# BMSMaster.net
KiCad netlist of a schematic drawn in EAGLE
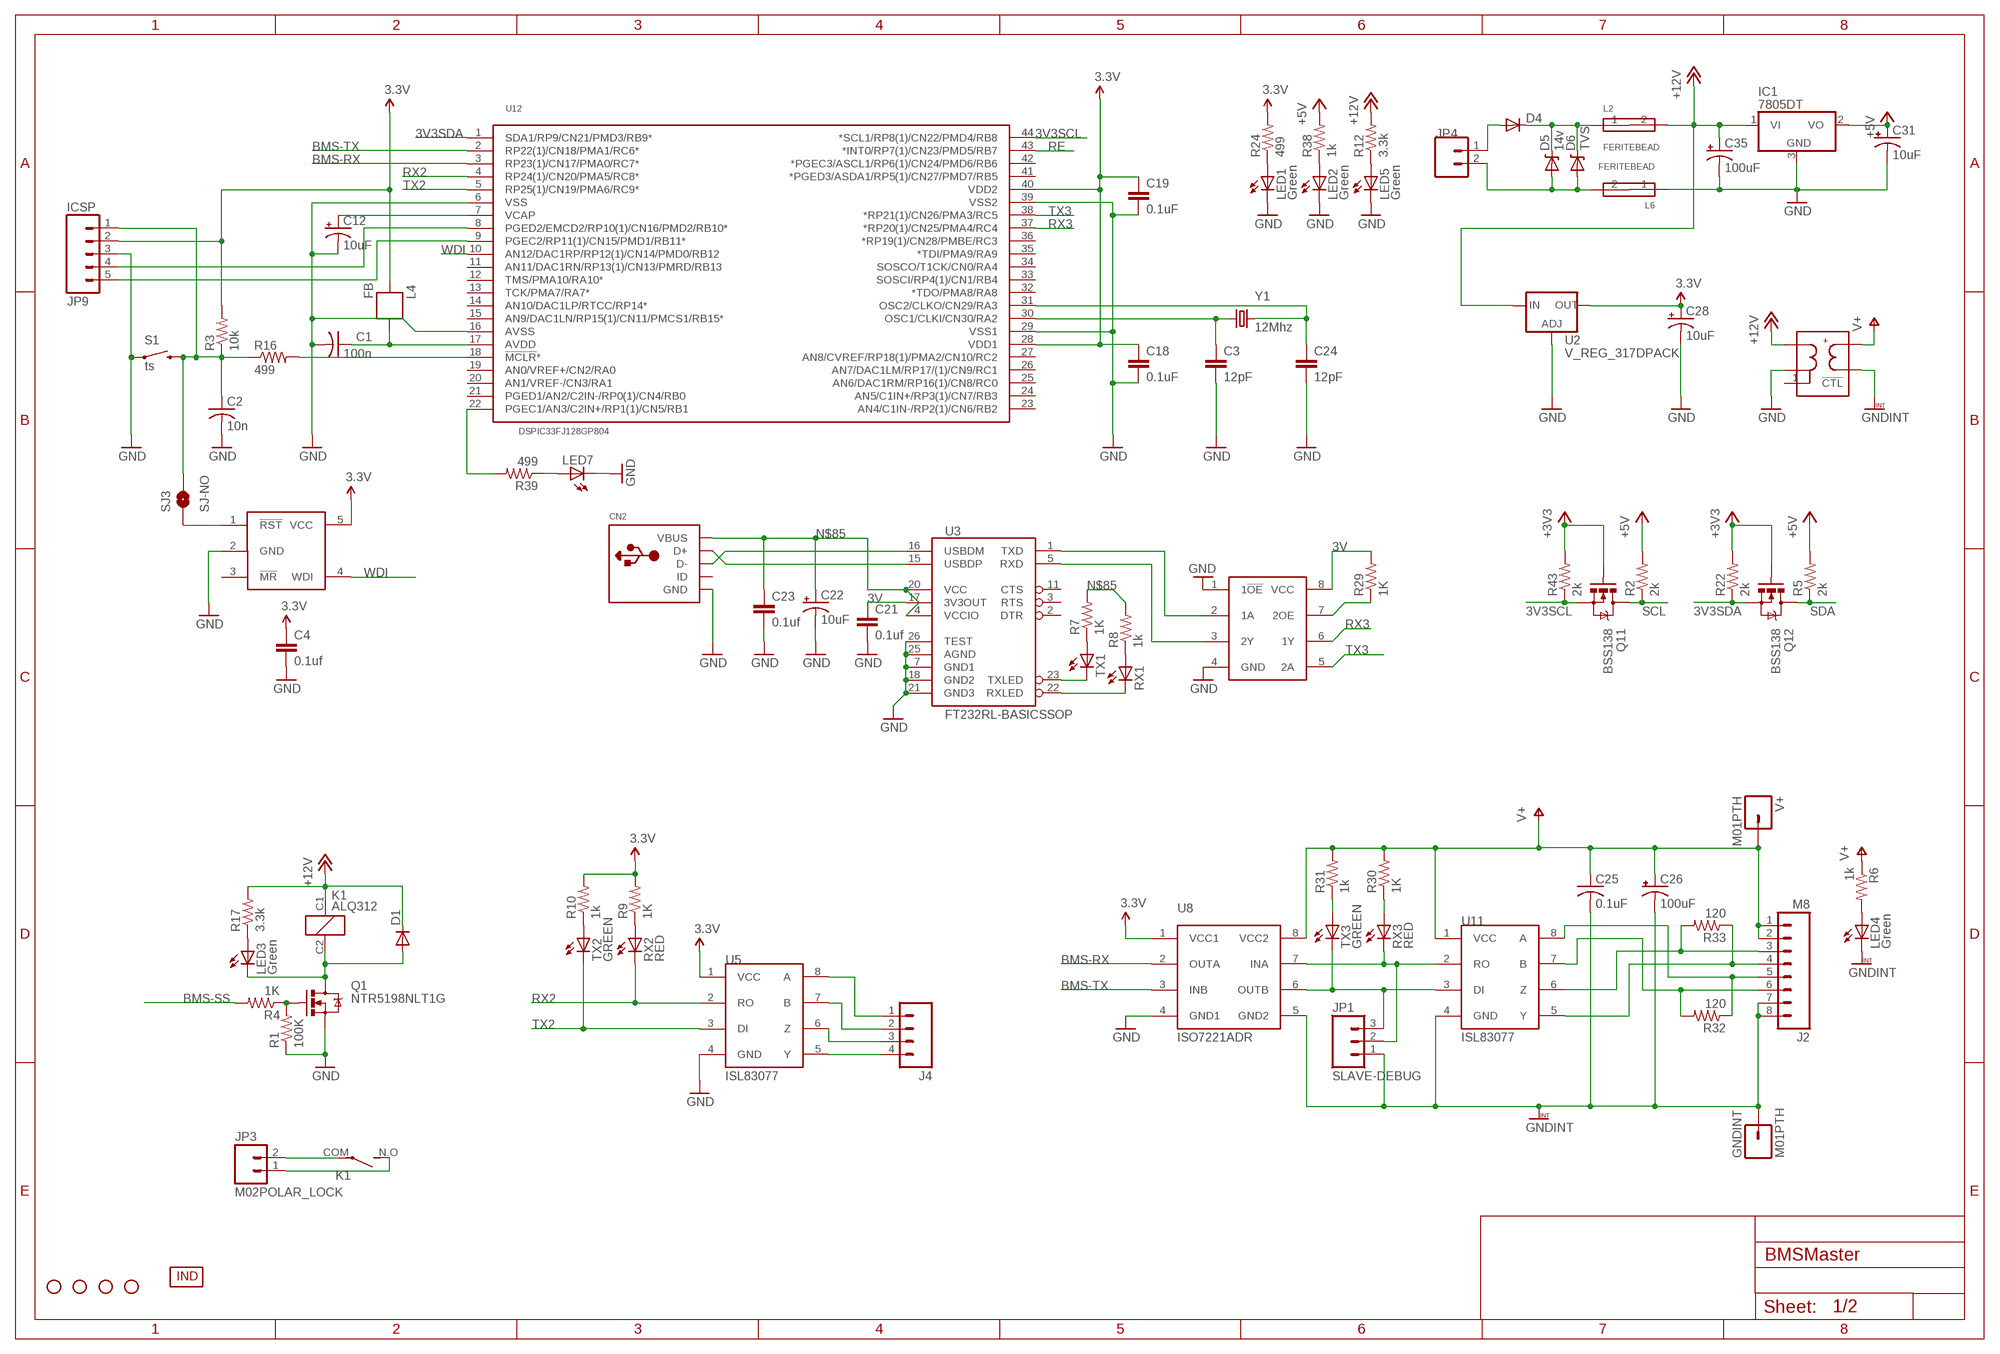
[diagram p0: schematic, sheet 1]
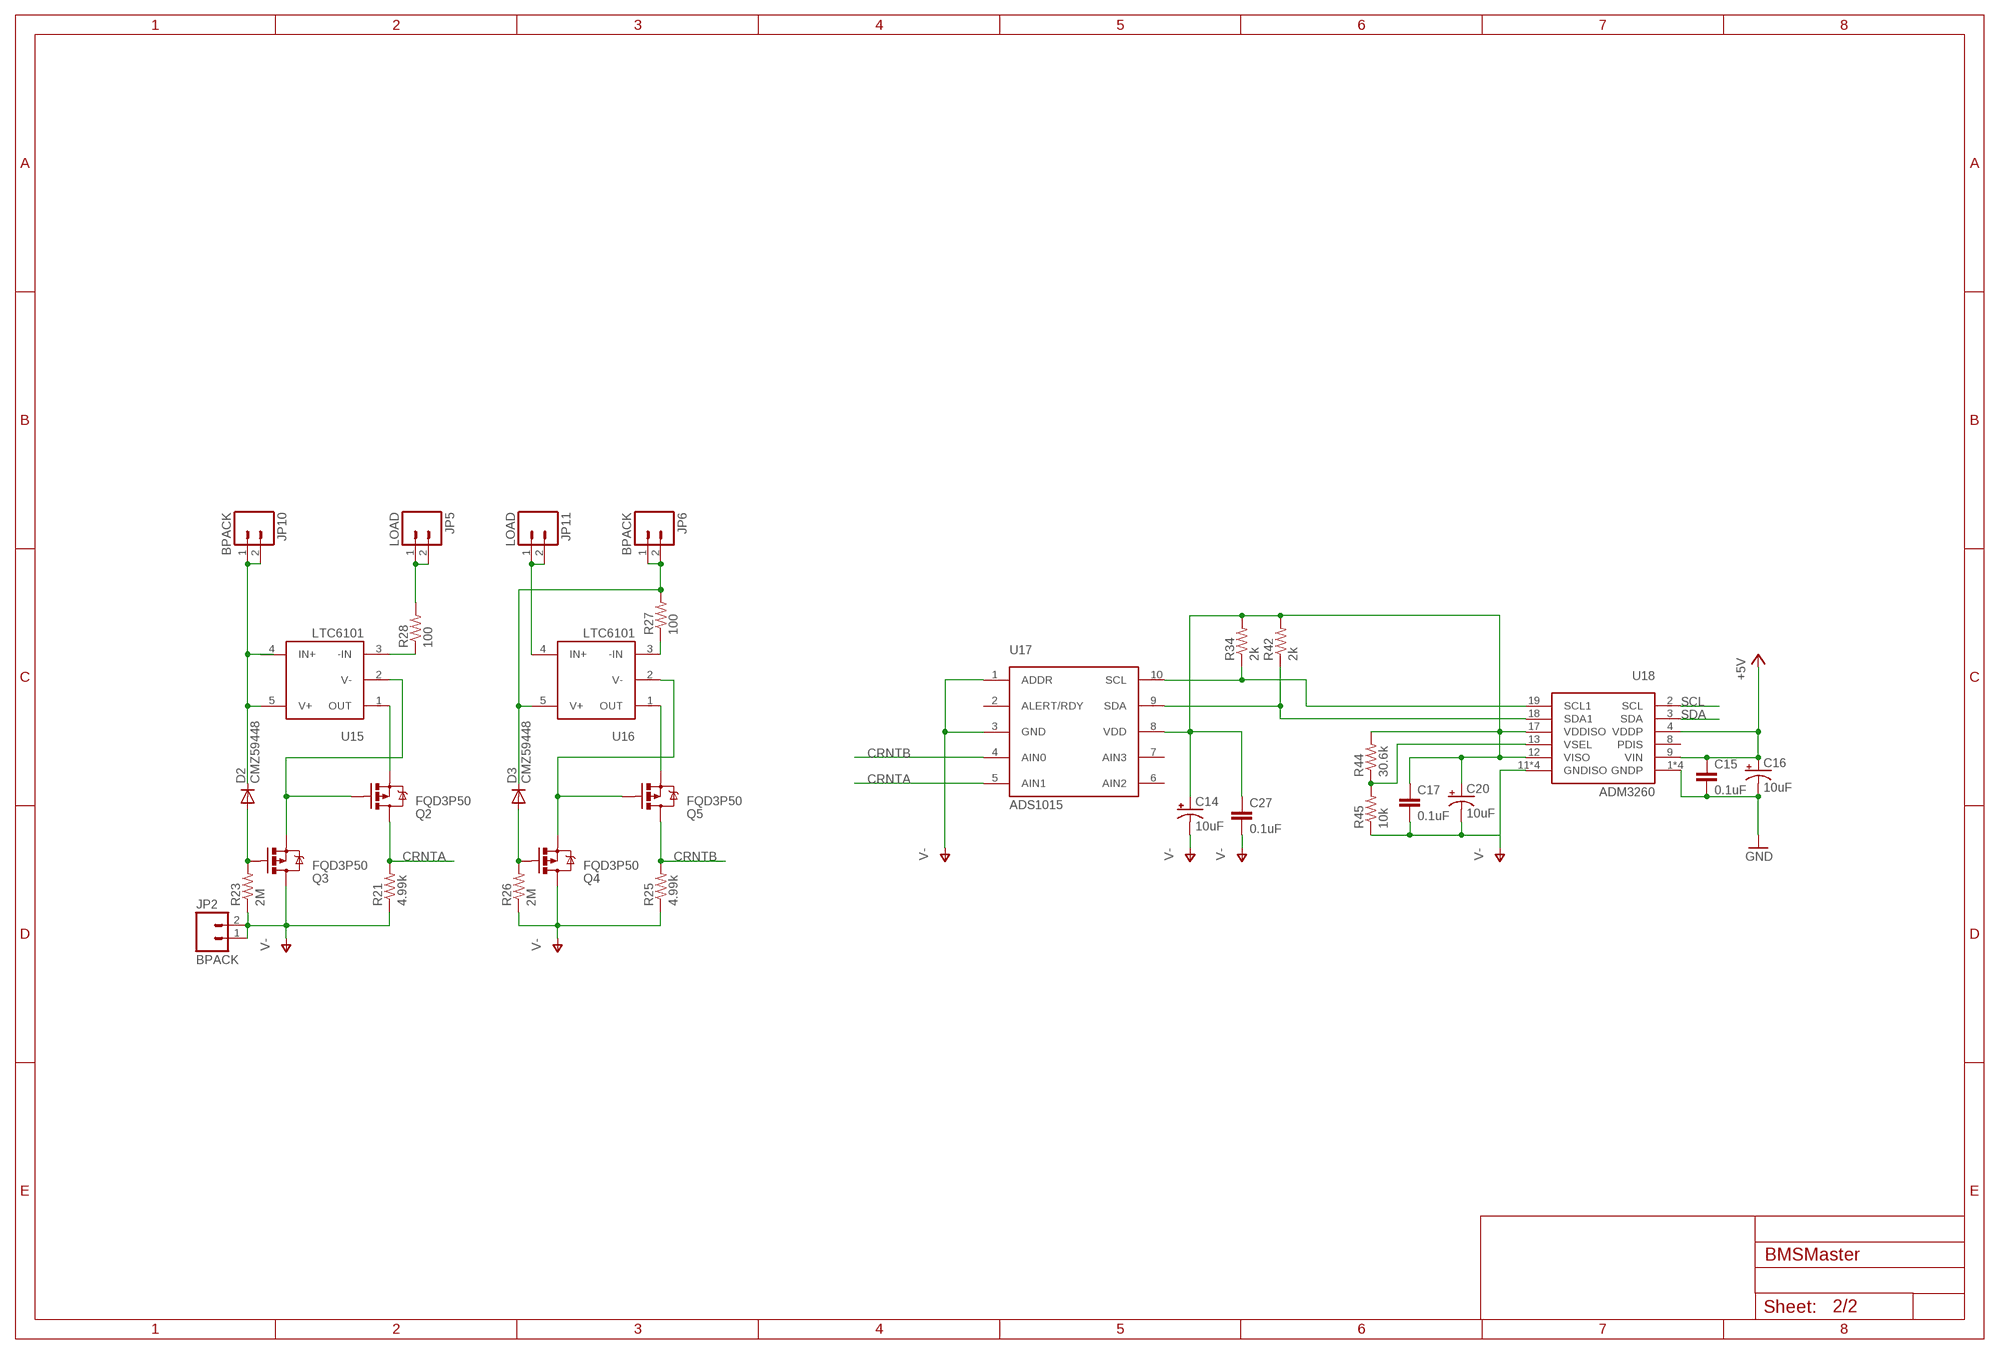
[diagram p1: schematic, sheet 2]

(export (version "E")
  (design (tool "Eeschema 10.0.6"))
  (components
    (comp (ref "C14")
      (value "10uF")
      (footprint "eagle-import:EIA3216")
      (libsource (lib "eagle-import") (part "SparkFun-Capacitors_CAP_POL1206"))
    )
    (comp (ref "C15")
      (value "0.1uF")
      (footprint "eagle-import:0805")
      (libsource (lib "eagle-import") (part "SparkFun-Capacitors_CAP0805"))
    )
    (comp (ref "C16")
      (value "10uF")
      (footprint "eagle-import:EIA3216")
      (libsource (lib "eagle-import") (part "SparkFun-Capacitors_CAP_POL1206"))
    )
    (comp (ref "C17")
      (value "0.1uF")
      (footprint "eagle-import:0805")
      (libsource (lib "eagle-import") (part "SparkFun-Capacitors_CAP0805"))
    )
    (comp (ref "C20")
      (value "10uF")
      (footprint "eagle-import:EIA3216")
      (libsource (lib "eagle-import") (part "SparkFun-Capacitors_CAP_POL1206"))
    )
    (comp (ref "C27")
      (value "0.1uF")
      (footprint "eagle-import:0805")
      (libsource (lib "eagle-import") (part "SparkFun-Capacitors_CAP0805"))
    )
    (comp (ref "D2")
      (value "CMZ59448")
      (footprint "eagle-import:DIODE-HV")
      (libsource (lib "eagle-import") (part "DIODEHV"))
    )
    (comp (ref "D3")
      (value "CMZ59448")
      (footprint "eagle-import:DIODE-HV")
      (libsource (lib "eagle-import") (part "DIODEHV"))
    )
    (comp (ref "JP2")
      (value "BPACK")
      (footprint "eagle-import:MOLEX-1X2_LOCK")
      (libsource (lib "eagle-import") (part "M02POLAR_LOCK"))
    )
    (comp (ref "JP5")
      (value "LOAD")
      (footprint "eagle-import:MOLEX-1X2_LOCK")
      (libsource (lib "eagle-import") (part "M02POLAR_LOCK"))
    )
    (comp (ref "JP6")
      (value "BPACK")
      (footprint "eagle-import:MOLEX-1X2_LOCK")
      (libsource (lib "eagle-import") (part "M02POLAR_LOCK"))
    )
    (comp (ref "JP10")
      (value "BPACK")
      (footprint "eagle-import:MOLEX-1X2_LOCK")
      (libsource (lib "eagle-import") (part "M02POLAR_LOCK"))
    )
    (comp (ref "JP11")
      (value "LOAD")
      (footprint "eagle-import:MOLEX-1X2_LOCK")
      (libsource (lib "eagle-import") (part "M02POLAR_LOCK"))
    )
    (comp (ref "Q2")
      (value "FQD3P50")
      (footprint "eagle-import:DPAK")
      (libsource (lib "eagle-import") (part "FQD3P50"))
    )
    (comp (ref "Q3")
      (value "FQD3P50")
      (footprint "eagle-import:DPAK")
      (libsource (lib "eagle-import") (part "FQD3P50"))
    )
    (comp (ref "Q4")
      (value "FQD3P50")
      (footprint "eagle-import:DPAK")
      (libsource (lib "eagle-import") (part "FQD3P50"))
    )
    (comp (ref "Q5")
      (value "FQD3P50")
      (footprint "eagle-import:DPAK")
      (libsource (lib "eagle-import") (part "FQD3P50"))
    )
    (comp (ref "R21")
      (value "4.99k")
      (footprint "eagle-import:1206")
      (libsource (lib "eagle-import") (part "RESISTOR1206"))
    )
    (comp (ref "R23")
      (value "2M")
      (footprint "eagle-import:1206")
      (libsource (lib "eagle-import") (part "RESISTOR1206"))
    )
    (comp (ref "R25")
      (value "4.99k")
      (footprint "eagle-import:1206")
      (libsource (lib "eagle-import") (part "RESISTOR1206"))
    )
    (comp (ref "R26")
      (value "2M")
      (footprint "eagle-import:1206")
      (libsource (lib "eagle-import") (part "RESISTOR1206"))
    )
    (comp (ref "R27")
      (value "100")
      (footprint "eagle-import:1206")
      (libsource (lib "eagle-import") (part "RESISTOR1206"))
    )
    (comp (ref "R28")
      (value "100")
      (footprint "eagle-import:1206")
      (libsource (lib "eagle-import") (part "RESISTOR1206"))
    )
    (comp (ref "R34")
      (value "2k")
      (footprint "eagle-import:0805")
      (libsource (lib "eagle-import") (part "RESISTOR0805-RES"))
    )
    (comp (ref "R42")
      (value "2k")
      (footprint "eagle-import:0805")
      (libsource (lib "eagle-import") (part "RESISTOR0805-RES"))
    )
    (comp (ref "R44")
      (value "30.6k")
      (footprint "eagle-import:0805")
      (libsource (lib "eagle-import") (part "RESISTOR0805-RES"))
    )
    (comp (ref "R45")
      (value "10k")
      (footprint "eagle-import:0805")
      (libsource (lib "eagle-import") (part "RESISTOR0805-RES"))
    )
    (comp (ref "U15")
      (value "LTC6101")
      (footprint "eagle-import:SOT23-5")
      (libsource (lib "eagle-import") (part "LTC6101"))
    )
    (comp (ref "U16")
      (value "LTC6101")
      (footprint "eagle-import:SOT23-5")
      (libsource (lib "eagle-import") (part "LTC6101"))
    )
    (comp (ref "U17")
      (value "ADS1015")
      (footprint "eagle-import:MSOP-10")
      (libsource (lib "eagle-import") (part "ADS1015"))
    )
    (comp (ref "U18")
      (value "ADM3260")
      (footprint "eagle-import:SSOP-20")
      (libsource (lib "eagle-import") (part "ADM3260"))
    )
    (comp (ref "C1")
      (value "100n")
      (footprint "eagle-import:C0805")
      (libsource (lib "eagle-import") (part "C-USC0805"))
    )
    (comp (ref "C2")
      (value "10n")
      (footprint "eagle-import:C0805")
      (libsource (lib "eagle-import") (part "C-USC0805"))
    )
    (comp (ref "C3")
      (value "12pF")
      (footprint "eagle-import:0805")
      (libsource (lib "eagle-import") (part "SparkFun-Capacitors_CAP0805"))
    )
    (comp (ref "C4")
      (value "0.1uf")
      (footprint "eagle-import:0805")
      (libsource (lib "eagle-import") (part "CAP0805"))
    )
    (comp (ref "C12")
      (value "10uF")
      (footprint "eagle-import:EIA3216")
      (libsource (lib "eagle-import") (part "10UF-TANT"))
    )
    (comp (ref "C18")
      (value "0.1uF")
      (footprint "eagle-import:0805")
      (libsource (lib "eagle-import") (part "SparkFun-Capacitors_CAP0805"))
    )
    (comp (ref "C19")
      (value "0.1uF")
      (footprint "eagle-import:0805")
      (libsource (lib "eagle-import") (part "SparkFun-Capacitors_CAP0805"))
    )
    (comp (ref "C21")
      (value "0.1uf")
      (footprint "eagle-import:0805")
      (libsource (lib "eagle-import") (part "CAP0805"))
    )
    (comp (ref "C22")
      (value "10uF")
      (footprint "eagle-import:EIA3216")
      (libsource (lib "eagle-import") (part "CAP_POL1206"))
    )
    (comp (ref "C23")
      (value "0.1uf")
      (footprint "eagle-import:0805")
      (libsource (lib "eagle-import") (part "CAP0805"))
    )
    (comp (ref "C24")
      (value "12pF")
      (footprint "eagle-import:0805")
      (libsource (lib "eagle-import") (part "SparkFun-Capacitors_CAP0805"))
    )
    (comp (ref "C25")
      (value "0.1uF")
      (footprint "eagle-import:C0805")
      (libsource (lib "eagle-import") (part "rcl_C-USC0805"))
    )
    (comp (ref "C26")
      (value "100uF")
      (footprint "eagle-import:C_6032-28W")
      (libsource (lib "eagle-import") (part "rcl_CPOL-USC/6032-28W"))
    )
    (comp (ref "C28")
      (value "10uF")
      (footprint "eagle-import:POLC1206")
      (libsource (lib "eagle-import") (part "POLCAP"))
    )
    (comp (ref "C31")
      (value "10uF")
      (footprint "eagle-import:EIA3216")
      (libsource (lib "eagle-import") (part "10UF-16V-10%(TANT)"))
    )
    (comp (ref "C35")
      (value "100uF")
      (footprint "eagle-import:CT7343")
      (libsource (lib "eagle-import") (part "CPOL-USCT7343"))
    )
    (comp (ref "CN2")
      (value "USBMOLEX")
      (footprint "eagle-import:USB-MINIB-THM-MOLEX")
      (libsource (lib "eagle-import") (part "USBMOLEX"))
    )
    (comp (ref "D1")
      (value "DIODESMB")
      (footprint "eagle-import:SMB-DIODE")
      (libsource (lib "eagle-import") (part "DIODESMB"))
    )
    (comp (ref "D4")
      (value "DIODESMA")
      (footprint "eagle-import:SMA-DIODE")
      (libsource (lib "eagle-import") (part "DIODESMA"))
    )
    (comp (ref "D5")
      (value "14v")
      (footprint "eagle-import:SMB-DIODE")
      (libsource (lib "eagle-import") (part "DIODE-ZENERSMB"))
    )
    (comp (ref "D6")
      (value "TVS")
      (footprint "eagle-import:DO-214AC")
      (libsource (lib "eagle-import") (part "TVS"))
    )
    (comp (ref "GNDINT")
      (value "M01PTH")
      (footprint "eagle-import:1X01")
      (libsource (lib "eagle-import") (part "M01PTH"))
    )
    (comp (ref "IC1")
      (value "7805DT")
      (footprint "eagle-import:TO252")
      (libsource (lib "eagle-import") (part "78DT05"))
    )
    (comp (ref "J2")
      (value "M8")
      (footprint "eagle-import:75869-132LF")
      (libsource (lib "eagle-import") (part "M8"))
    )
    (comp (ref "J4")
      (value "M04POLAR_LOCK")
      (footprint "eagle-import:MOLEX-1X4_LOCK")
      (libsource (lib "eagle-import") (part "M04POLAR_LOCK"))
    )
    (comp (ref "JP1")
      (value "SLAVE-DEBUG")
      (footprint "eagle-import:1X03_LOCK_LONGPADS")
      (libsource (lib "eagle-import") (part "M03LOCK_LONGPADS"))
    )
    (comp (ref "JP3")
      (value "M02POLAR_LOCK")
      (footprint "eagle-import:MOLEX-1X2_LOCK")
      (libsource (lib "eagle-import") (part "M02POLAR_LOCK"))
    )
    (comp (ref "JP4")
      (value "M02POLAR_LOCK")
      (footprint "eagle-import:MOLEX-1X2_LOCK")
      (libsource (lib "eagle-import") (part "M02POLAR_LOCK"))
    )
    (comp (ref "JP9")
      (value "ICSP")
      (footprint "eagle-import:1X05_LOCK_LONGPADS")
      (libsource (lib "eagle-import") (part "M05LOCK_LONGPADS"))
    )
    (comp (ref "K1")
      (value "ALQ312")
      (footprint "eagle-import:ALQ312")
      (libsource (lib "eagle-import") (part "ALQ312"))
    )
    (comp (ref "L2")
      (value "FERITEBEAD")
      (footprint "eagle-import:0603")
      (libsource (lib "eagle-import") (part "FERITEBEAD"))
    )
    (comp (ref "L4")
      (value "FB")
      (footprint "eagle-import:0603")
      (libsource (lib "eagle-import") (part "FB"))
    )
    (comp (ref "L6")
      (value "FERITEBEAD")
      (footprint "eagle-import:0603")
      (libsource (lib "eagle-import") (part "FERITEBEAD"))
    )
    (comp (ref "LED1")
      (value "Green")
      (footprint "eagle-import:CHIPLED_0805")
      (libsource (lib "eagle-import") (part "LEDCHIPLED_0805"))
    )
    (comp (ref "LED2")
      (value "Green")
      (footprint "eagle-import:CHIPLED_0805")
      (libsource (lib "eagle-import") (part "LEDCHIPLED_0805"))
    )
    (comp (ref "LED3")
      (value "Green")
      (footprint "eagle-import:CHIPLED_0805")
      (libsource (lib "eagle-import") (part "LEDCHIPLED_0805"))
    )
    (comp (ref "LED4")
      (value "Green")
      (footprint "eagle-import:CHIPLED_0805")
      (libsource (lib "eagle-import") (part "LEDCHIPLED_0805"))
    )
    (comp (ref "LED5")
      (value "Green")
      (footprint "eagle-import:CHIPLED_0805")
      (libsource (lib "eagle-import") (part "LEDCHIPLED_0805"))
    )
    (comp (ref "LED7")
      (value "LEDCHIP-LED0805")
      (footprint "eagle-import:CHIP-LED0805")
      (libsource (lib "eagle-import") (part "LEDCHIP-LED0805"))
    )
    (comp (ref "Q1")
      (value "NTR5198NLT1G")
      (footprint "eagle-import:SOT23")
      (libsource (lib "eagle-import") (part "MOSFET-NCHANNELBSS123LT1G"))
    )
    (comp (ref "Q11")
      (value "BSS138")
      (footprint "eagle-import:SOT23-3")
      (libsource (lib "eagle-import") (part "MOSFET-NCHANNELSMD"))
    )
    (comp (ref "Q12")
      (value "BSS138")
      (footprint "eagle-import:SOT23-3")
      (libsource (lib "eagle-import") (part "MOSFET-NCHANNELSMD"))
    )
    (comp (ref "R1")
      (value "100K")
      (footprint "eagle-import:R0805")
      (libsource (lib "eagle-import") (part "R-US_R0805"))
    )
    (comp (ref "R2")
      (value "2k")
      (footprint "eagle-import:R0805")
      (libsource (lib "eagle-import") (part "R-US_R0805"))
    )
    (comp (ref "R3")
      (value "10k")
      (footprint "eagle-import:0805")
      (libsource (lib "eagle-import") (part "RESISTOR0805-RES"))
    )
    (comp (ref "R4")
      (value "1K")
      (footprint "eagle-import:R0805")
      (libsource (lib "eagle-import") (part "R-US_R0805"))
    )
    (comp (ref "R5")
      (value "2k")
      (footprint "eagle-import:R0805")
      (libsource (lib "eagle-import") (part "R-US_R0805"))
    )
    (comp (ref "R6")
      (value "1k")
      (footprint "eagle-import:R0805")
      (libsource (lib "eagle-import") (part "R-US_R0805"))
    )
    (comp (ref "R7")
      (value "1K")
      (footprint "eagle-import:R0805")
      (libsource (lib "eagle-import") (part "R-US_R0805"))
    )
    (comp (ref "R8")
      (value "1k")
      (footprint "eagle-import:R0805")
      (libsource (lib "eagle-import") (part "R-US_R0805"))
    )
    (comp (ref "R9")
      (value "1K")
      (footprint "eagle-import:R0805")
      (libsource (lib "eagle-import") (part "R-US_R0805"))
    )
    (comp (ref "R10")
      (value "1k")
      (footprint "eagle-import:R0805")
      (libsource (lib "eagle-import") (part "R-US_R0805"))
    )
    (comp (ref "R12")
      (value "3.3k")
      (footprint "eagle-import:R0805")
      (libsource (lib "eagle-import") (part "R-US_R0805"))
    )
    (comp (ref "R16")
      (value "499")
      (footprint "eagle-import:0805")
      (libsource (lib "eagle-import") (part "SparkFun-Resistors_RESISTOR0805-RES"))
    )
    (comp (ref "R17")
      (value "3.3k")
      (footprint "eagle-import:R0805")
      (libsource (lib "eagle-import") (part "R-US_R0805"))
    )
    (comp (ref "R22")
      (value "2k")
      (footprint "eagle-import:R0805")
      (libsource (lib "eagle-import") (part "R-US_R0805"))
    )
    (comp (ref "R24")
      (value "499")
      (footprint "eagle-import:R0805")
      (libsource (lib "eagle-import") (part "R-US_R0805"))
    )
    (comp (ref "R29")
      (value "1K")
      (footprint "eagle-import:R0805")
      (libsource (lib "eagle-import") (part "R-US_R0805"))
    )
    (comp (ref "R30")
      (value "1K")
      (footprint "eagle-import:R0805")
      (libsource (lib "eagle-import") (part "R-US_R0805"))
    )
    (comp (ref "R31")
      (value "1k")
      (footprint "eagle-import:R0805")
      (libsource (lib "eagle-import") (part "R-US_R0805"))
    )
    (comp (ref "R32")
      (value "120")
      (footprint "eagle-import:R0805")
      (libsource (lib "eagle-import") (part "R-US_R0805"))
    )
    (comp (ref "R33")
      (value "120")
      (footprint "eagle-import:R0805")
      (libsource (lib "eagle-import") (part "R-US_R0805"))
    )
    (comp (ref "R38")
      (value "1k")
      (footprint "eagle-import:R0805")
      (libsource (lib "eagle-import") (part "R-US_R0805"))
    )
    (comp (ref "R39")
      (value "499")
      (footprint "eagle-import:0805")
      (libsource (lib "eagle-import") (part "RESISTOR0805-RES"))
    )
    (comp (ref "R43")
      (value "2k")
      (footprint "eagle-import:R0805")
      (libsource (lib "eagle-import") (part "R-US_R0805"))
    )
    (comp (ref "RX1")
      (value "LEDCHIPLED_0805")
      (footprint "eagle-import:CHIPLED_0805")
      (libsource (lib "eagle-import") (part "LEDCHIPLED_0805"))
    )
    (comp (ref "RX2")
      (value "RED")
      (footprint "eagle-import:CHIPLED_0805")
      (libsource (lib "eagle-import") (part "LEDCHIPLED_0805"))
    )
    (comp (ref "RX3")
      (value "RED")
      (footprint "eagle-import:CHIPLED_0805")
      (libsource (lib "eagle-import") (part "LEDCHIPLED_0805"))
    )
    (comp (ref "S1")
      (value "ts")
      (footprint "eagle-import:TACTILE-PTH-SIDEEZ")
      (libsource (lib "eagle-import") (part "SWITCH-MOMENTARY-2SIDE_EZ"))
    )
    (comp (ref "SJ3")
      (value "SJ-NO")
      (footprint "eagle-import:SJ_2S-NO")
      (libsource (lib "eagle-import") (part "SOLDERJUMPERNO"))
    )
    (comp (ref "STANDOFF1")
      (value "STAND-OFF")
      (footprint "eagle-import:STAND-OFF")
      (libsource (lib "eagle-import") (part "STAND-OFF"))
    )
    (comp (ref "STANDOFF2")
      (value "STAND-OFF")
      (footprint "eagle-import:STAND-OFF")
      (libsource (lib "eagle-import") (part "STAND-OFF"))
    )
    (comp (ref "STANDOFF3")
      (value "STAND-OFF")
      (footprint "eagle-import:STAND-OFF")
      (libsource (lib "eagle-import") (part "STAND-OFF"))
    )
    (comp (ref "STANDOFF4")
      (value "STAND-OFF")
      (footprint "eagle-import:STAND-OFF")
      (libsource (lib "eagle-import") (part "STAND-OFF"))
    )
    (comp (ref "TX1")
      (value "LEDCHIPLED_0805")
      (footprint "eagle-import:CHIPLED_0805")
      (libsource (lib "eagle-import") (part "LEDCHIPLED_0805"))
    )
    (comp (ref "TX2")
      (value "GREEN")
      (footprint "eagle-import:CHIPLED_0805")
      (libsource (lib "eagle-import") (part "LEDCHIPLED_0805"))
    )
    (comp (ref "TX3")
      (value "GREEN")
      (footprint "eagle-import:CHIPLED_0805")
      (libsource (lib "eagle-import") (part "LEDCHIPLED_0805"))
    )
    (comp (ref "U$1")
      (value "INDPK1")
      (footprint "eagle-import:PICKIT-PIN-1")
      (libsource (lib "eagle-import") (part "INDPK1"))
    )
    (comp (ref "U2")
      (value "V_REG_317DPACK")
      (footprint "eagle-import:V-REG_DPACK")
      (libsource (lib "eagle-import") (part "V_REG_317DPACK"))
    )
    (comp (ref "U3")
      (value "FT232RL-BASICSSOP")
      (footprint "eagle-import:SSOP28DB")
      (libsource (lib "eagle-import") (part "FT232RL-BASICSSOP"))
    )
    (comp (ref "U4")
      (value "SN74LVC2G241DCTR")
      (footprint "eagle-import:VFSOP-8")
      (libsource (lib "eagle-import") (part "SN74LVC2G241DCTR"))
    )
    (comp (ref "U5")
      (value "ISL83077")
      (footprint "eagle-import:SO08")
      (libsource (lib "eagle-import") (part "ISL83077"))
    )
    (comp (ref "U8")
      (value "ISO7221ADR")
      (footprint "eagle-import:SOIC-8")
      (libsource (lib "eagle-import") (part "ISO7221ADR"))
    )
    (comp (ref "U9")
      (value "MAX823")
      (footprint "eagle-import:SOT23-5L")
      (libsource (lib "eagle-import") (part "MAX823"))
    )
    (comp (ref "U11")
      (value "ISL83077")
      (footprint "eagle-import:SO08")
      (libsource (lib "eagle-import") (part "ISL83077"))
    )
    (comp (ref "U12")
      (value "DSPIC33FJ128GP804")
      (footprint "eagle-import:TQFP-44")
      (libsource (lib "eagle-import") (part "DSPIC33FJ128GP804"))
    )
    (comp (ref "U21")
      (value "REC7.5-1205SRW/H2/A/M")
      (footprint "eagle-import:24DIPMOD-8LEAD")
      (libsource (lib "eagle-import") (part "REC7.5-1205SRW/H2/A/M"))
    )
    (comp (ref "V+")
      (value "M01PTH")
      (footprint "eagle-import:1X01")
      (libsource (lib "eagle-import") (part "M01PTH"))
    )
    (comp (ref "Y1")
      (value "12Mhz")
      (footprint "eagle-import:CRYSTAL-SMD-5X3")
      (libsource (lib "eagle-import") (part "CRYSTAL5X3"))
    )
  )
  (nets
    (net (code "1") (name "+3V3") (class "Default")
      (node (ref "Q11") (pin "1") (pinfunction "G_1") (pintype "passive"))
      (node (ref "Q12") (pin "1") (pinfunction "G_1") (pintype "passive"))
      (node (ref "R22") (pin "2") (pinfunction "2_2") (pintype "passive"))
      (node (ref "R43") (pin "2") (pinfunction "2_2") (pintype "passive"))
    )
    (net (code "2") (name "+5V") (class "Default")
      (node (ref "C15") (pin "1") (pinfunction "1_1") (pintype "passive"))
      (node (ref "C16") (pin "A") (pinfunction "+_A") (pintype "passive"))
      (node (ref "C31") (pin "A") (pinfunction "+_A") (pintype "passive"))
      (node (ref "IC1") (pin "2") (pinfunction "VO_2") (pintype "passive"))
      (node (ref "R2") (pin "2") (pinfunction "2_2") (pintype "passive"))
      (node (ref "R38") (pin "2") (pinfunction "2_2") (pintype "passive"))
      (node (ref "R5") (pin "2") (pinfunction "2_2") (pintype "passive"))
      (node (ref "U18") (pin "4") (pinfunction "VDDP_4") (pintype "bidirectional"))
      (node (ref "U18") (pin "9") (pinfunction "VIN_9") (pintype "bidirectional"))
    )
    (net (code "3") (name "+12V") (class "Default")
      (node (ref "C35") (pin "+") (pinfunction "+_+") (pintype "passive"))
      (node (ref "D1") (pin "C") (pinfunction "C_C") (pintype "passive"))
      (node (ref "IC1") (pin "1") (pinfunction "VI_1") (pintype "input"))
      (node (ref "K1") (pin "C1") (pinfunction "+_C1") (pintype "passive"))
      (node (ref "L2") (pin "2") (pinfunction "P$2_2") (pintype "bidirectional"))
      (node (ref "R12") (pin "2") (pinfunction "2_2") (pintype "passive"))
      (node (ref "R17") (pin "2") (pinfunction "2_2") (pintype "passive"))
      (node (ref "U2") (pin "3") (pinfunction "IN_3") (pintype "input"))
      (node (ref "U21") (pin "22") (pinfunction "VIN+_22") (pintype "bidirectional"))
      (node (ref "U21") (pin "23") (pinfunction "VIN+_23") (pintype "bidirectional"))
    )
    (net (code "4") (name "3.3V") (class "Default")
      (node (ref "C18") (pin "1") (pinfunction "1_1") (pintype "passive"))
      (node (ref "C19") (pin "1") (pinfunction "1_1") (pintype "passive"))
      (node (ref "C28") (pin "1") (pinfunction "+_1") (pintype "passive"))
      (node (ref "C4") (pin "1") (pinfunction "1_1") (pintype "passive"))
      (node (ref "JP9") (pin "2") (pinfunction "2_2") (pintype "passive"))
      (node (ref "L4") (pin "2") (pinfunction "P$2_2") (pintype "bidirectional"))
      (node (ref "R10") (pin "2") (pinfunction "2_2") (pintype "passive"))
      (node (ref "R24") (pin "2") (pinfunction "2_2") (pintype "passive"))
      (node (ref "R3") (pin "2") (pinfunction "2_2") (pintype "passive"))
      (node (ref "R9") (pin "2") (pinfunction "2_2") (pintype "passive"))
      (node (ref "U12") (pin "28") (pinfunction "VDD1_28") (pintype "bidirectional"))
      (node (ref "U12") (pin "40") (pinfunction "VDD2_40") (pintype "bidirectional"))
      (node (ref "U2") (pin "4") (pinfunction "OUT_4") (pintype "output"))
      (node (ref "U5") (pin "1") (pinfunction "VCC_1") (pintype "bidirectional"))
      (node (ref "U8") (pin "1") (pinfunction "VCC1_1") (pintype "bidirectional"))
      (node (ref "U9") (pin "5") (pinfunction "VCC_5") (pintype "bidirectional"))
    )
    (net (code "5") (name "3V") (class "Default")
      (node (ref "C21") (pin "1") (pinfunction "1_1") (pintype "passive"))
      (node (ref "R29") (pin "2") (pinfunction "2_2") (pintype "passive"))
      (node (ref "U3") (pin "17") (pinfunction "3V3OUT_17") (pintype "output"))
      (node (ref "U4") (pin "8") (pinfunction "VCC_8") (pintype "bidirectional"))
    )
    (net (code "6") (name "3V3SCL") (class "Default")
      (node (ref "Q11") (pin "2") (pinfunction "S_2") (pintype "passive"))
      (node (ref "R43") (pin "1") (pinfunction "1_1") (pintype "passive"))
      (node (ref "U12") (pin "44") (pinfunction "*SCL1/RP8(1)/CN22/PMD4/RB8_44") (pintype "bidirectional"))
    )
    (net (code "7") (name "3V3SDA") (class "Default")
      (node (ref "Q12") (pin "2") (pinfunction "S_2") (pintype "passive"))
      (node (ref "R22") (pin "1") (pinfunction "1_1") (pintype "passive"))
      (node (ref "U12") (pin "1") (pinfunction "SDA1/RP9/CN21/PMD3/RB9*_1") (pintype "bidirectional"))
    )
    (net (code "8") (name "BMS-RX") (class "Default")
      (node (ref "U12") (pin "3") (pinfunction "RP23(1)/CN17/PMA0/RC7*_3") (pintype "bidirectional"))
      (node (ref "U8") (pin "2") (pinfunction "OUTA_2") (pintype "bidirectional"))
    )
    (net (code "9") (name "BMS-SS") (class "Default")
      (node (ref "R4") (pin "2") (pinfunction "2_2") (pintype "passive"))
    )
    (net (code "10") (name "BMS-TX") (class "Default")
      (node (ref "U12") (pin "2") (pinfunction "RP22(1)/CN18/PMA1/RC6*_2") (pintype "bidirectional"))
      (node (ref "U8") (pin "3") (pinfunction "INB_3") (pintype "bidirectional"))
    )
    (net (code "11") (name "CRNTA") (class "Default")
      (node (ref "Q2") (pin "2") (pinfunction "D_2") (pintype "passive"))
      (node (ref "R21") (pin "2") (pinfunction "2_2") (pintype "passive"))
      (node (ref "U17") (pin "5") (pinfunction "AIN1_5") (pintype "bidirectional"))
    )
    (net (code "12") (name "CRNTB") (class "Default")
      (node (ref "Q5") (pin "2") (pinfunction "D_2") (pintype "passive"))
      (node (ref "R25") (pin "2") (pinfunction "2_2") (pintype "passive"))
      (node (ref "U17") (pin "4") (pinfunction "AIN0_4") (pintype "bidirectional"))
    )
    (net (code "13") (name "GND") (class "Default")
      (node (ref "C1") (pin "2") (pinfunction "2_2") (pintype "passive"))
      (node (ref "C12") (pin "C") (pinfunction "-_C") (pintype "passive"))
      (node (ref "C15") (pin "2") (pinfunction "2_2") (pintype "passive"))
      (node (ref "C16") (pin "C") (pinfunction "-_C") (pintype "passive"))
      (node (ref "C18") (pin "2") (pinfunction "2_2") (pintype "passive"))
      (node (ref "C19") (pin "2") (pinfunction "2_2") (pintype "passive"))
      (node (ref "C2") (pin "2") (pinfunction "2_2") (pintype "passive"))
      (node (ref "C21") (pin "2") (pinfunction "2_2") (pintype "passive"))
      (node (ref "C22") (pin "C") (pinfunction "-_C") (pintype "passive"))
      (node (ref "C23") (pin "2") (pinfunction "2_2") (pintype "passive"))
      (node (ref "C24") (pin "2") (pinfunction "2_2") (pintype "passive"))
      (node (ref "C28") (pin "2") (pinfunction "-_2") (pintype "passive"))
      (node (ref "C3") (pin "2") (pinfunction "2_2") (pintype "passive"))
      (node (ref "C31") (pin "C") (pinfunction "-_C") (pintype "passive"))
      (node (ref "C35") (pin "-") (pinfunction "-_-") (pintype "passive"))
      (node (ref "C4") (pin "2") (pinfunction "2_2") (pintype "passive"))
      (node (ref "CN2") (pin "GND") (pinfunction "GND_GND") (pintype "power_in"))
      (node (ref "IC1") (pin "3") (pinfunction "GND_3") (pintype "passive"))
      (node (ref "JP9") (pin "3") (pinfunction "3_3") (pintype "passive"))
      (node (ref "L6") (pin "1") (pinfunction "P$1_1") (pintype "bidirectional"))
      (node (ref "LED1") (pin "C") (pinfunction "C_C") (pintype "passive"))
      (node (ref "LED2") (pin "C") (pinfunction "C_C") (pintype "passive"))
      (node (ref "LED5") (pin "C") (pinfunction "C_C") (pintype "passive"))
      (node (ref "LED7") (pin "C") (pinfunction "C_C") (pintype "passive"))
      (node (ref "Q1") (pin "2") (pinfunction "S_2") (pintype "passive"))
      (node (ref "R1") (pin "1") (pinfunction "1_1") (pintype "passive"))
      (node (ref "S1") (pin "1") (pinfunction "1_1") (pintype "passive"))
      (node (ref "U12") (pin "16") (pinfunction "AVSS_16") (pintype "bidirectional"))
      (node (ref "U12") (pin "29") (pinfunction "VSS1_29") (pintype "bidirectional"))
      (node (ref "U12") (pin "39") (pinfunction "VSS2_39") (pintype "bidirectional"))
      (node (ref "U12") (pin "6") (pinfunction "VSS_6") (pintype "bidirectional"))
      (node (ref "U18") (pin "1") (pinfunction "GNDP_1") (pintype "bidirectional"))
      (node (ref "U18") (pin "10") (pinfunction "GNDP_10") (pintype "bidirectional"))
      (node (ref "U18") (pin "5") (pinfunction "GNDP_5") (pintype "bidirectional"))
      (node (ref "U18") (pin "7") (pinfunction "GNDP_7") (pintype "bidirectional"))
      (node (ref "U2") (pin "1") (pinfunction "ADJ_1") (pintype "input"))
      (node (ref "U21") (pin "2") (pinfunction "VIN-_2") (pintype "bidirectional"))
      (node (ref "U21") (pin "3") (pinfunction "VIN-_3") (pintype "bidirectional"))
      (node (ref "U3") (pin "18") (pinfunction "GND2_18") (pintype "power_in"))
      (node (ref "U3") (pin "21") (pinfunction "GND3_21") (pintype "power_in"))
      (node (ref "U3") (pin "25") (pinfunction "AGND_25") (pintype "power_in"))
      (node (ref "U3") (pin "26") (pinfunction "TEST_26") (pintype "input"))
      (node (ref "U3") (pin "7") (pinfunction "GND1_7") (pintype "power_in"))
      (node (ref "U4") (pin "1") (pinfunction "1~{OE}_1") (pintype "bidirectional"))
      (node (ref "U4") (pin "4") (pinfunction "GND_4") (pintype "bidirectional"))
      (node (ref "U5") (pin "4") (pinfunction "GND_4") (pintype "bidirectional"))
      (node (ref "U8") (pin "4") (pinfunction "GND1_4") (pintype "bidirectional"))
      (node (ref "U9") (pin "2") (pinfunction "GND_2") (pintype "bidirectional"))
    )
    (net (code "14") (name "GNDINT") (class "Default")
      (node (ref "C25") (pin "2") (pinfunction "2_2") (pintype "passive"))
      (node (ref "C26") (pin "-") (pinfunction "-_-") (pintype "passive"))
      (node (ref "GNDINT") (pin "1") (pinfunction "1_1") (pintype "passive"))
      (node (ref "J2") (pin "7") (pinfunction "7_7") (pintype "passive"))
      (node (ref "J2") (pin "8") (pinfunction "8_8") (pintype "passive"))
      (node (ref "JP1") (pin "1") (pinfunction "1_1") (pintype "passive"))
      (node (ref "LED4") (pin "C") (pinfunction "C_C") (pintype "passive"))
      (node (ref "U11") (pin "4") (pinfunction "GND_4") (pintype "bidirectional"))
      (node (ref "U21") (pin "16") (pinfunction "VOUT-_16") (pintype "bidirectional"))
      (node (ref "U8") (pin "5") (pinfunction "GND2_5") (pintype "bidirectional"))
    )
    (net (code "15") (name "N$85") (class "Default")
      (node (ref "C22") (pin "A") (pinfunction "+_A") (pintype "passive"))
      (node (ref "C23") (pin "1") (pinfunction "1_1") (pintype "passive"))
      (node (ref "CN2") (pin "VBUS") (pinfunction "VBUS_VBUS") (pintype "power_in"))
      (node (ref "R7") (pin "2") (pinfunction "2_2") (pintype "passive"))
      (node (ref "R8") (pin "2") (pinfunction "2_2") (pintype "passive"))
      (node (ref "U3") (pin "20") (pinfunction "VCC_20") (pintype "power_in"))
      (node (ref "U3") (pin "4") (pinfunction "VCCIO_4") (pintype "power_in"))
    )
    (net (code "16") (name "Net-(C2-Pad1)") (class "Default")
      (node (ref "C2") (pin "1") (pinfunction "1_1") (pintype "passive"))
      (node (ref "JP9") (pin "1") (pinfunction "1_1") (pintype "passive"))
      (node (ref "R16") (pin "1") (pinfunction "1_1") (pintype "passive"))
      (node (ref "R3") (pin "1") (pinfunction "1_1") (pintype "passive"))
      (node (ref "S1") (pin "2") (pinfunction "2_2") (pintype "passive"))
      (node (ref "SJ3") (pin "2") (pinfunction "2_2") (pintype "passive"))
    )
    (net (code "17") (name "Net-(C12-+)") (class "Default")
      (node (ref "C12") (pin "A") (pinfunction "+_A") (pintype "passive"))
      (node (ref "U12") (pin "7") (pinfunction "VCAP_7") (pintype "bidirectional"))
    )
    (net (code "18") (name "Net-(C14-+)") (class "Default")
      (node (ref "C14") (pin "A") (pinfunction "+_A") (pintype "passive"))
      (node (ref "C17") (pin "1") (pinfunction "1_1") (pintype "passive"))
      (node (ref "C20") (pin "A") (pinfunction "+_A") (pintype "passive"))
      (node (ref "C27") (pin "1") (pinfunction "1_1") (pintype "passive"))
      (node (ref "R34") (pin "2") (pinfunction "2_2") (pintype "passive"))
      (node (ref "R42") (pin "2") (pinfunction "2_2") (pintype "passive"))
      (node (ref "R44") (pin "2") (pinfunction "2_2") (pintype "passive"))
      (node (ref "U17") (pin "8") (pinfunction "VDD_8") (pintype "bidirectional"))
      (node (ref "U18") (pin "12") (pinfunction "VISO_12") (pintype "bidirectional"))
      (node (ref "U18") (pin "17") (pinfunction "VDDISO_17") (pintype "bidirectional"))
    )
    (net (code "19") (name "Net-(D4-PadA)") (class "Default")
      (node (ref "D4") (pin "A") (pinfunction "A_A") (pintype "passive"))
      (node (ref "JP4") (pin "1") (pinfunction "1_1") (pintype "passive"))
    )
    (net (code "20") (name "Net-(JP5-Pad1)") (class "Default")
      (node (ref "JP5") (pin "1") (pinfunction "1_1") (pintype "passive"))
      (node (ref "JP5") (pin "2") (pinfunction "2_2") (pintype "passive"))
      (node (ref "R28") (pin "2") (pinfunction "2_2") (pintype "passive"))
    )
    (net (code "21") (name "Net-(K1A--)") (class "Default")
      (node (ref "D1") (pin "A") (pinfunction "A_A") (pintype "passive"))
      (node (ref "K1") (pin "C2") (pinfunction "-_C2") (pintype "passive"))
      (node (ref "LED3") (pin "C") (pinfunction "C_C") (pintype "passive"))
      (node (ref "Q1") (pin "3") (pinfunction "D_3") (pintype "passive"))
    )
    (net (code "22") (name "Net-(K1B-P)") (class "Default")
      (node (ref "JP3") (pin "2") (pinfunction "2_2") (pintype "passive"))
      (node (ref "K1") (pin "COM") (pinfunction "P_COM") (pintype "passive"))
    )
    (net (code "23") (name "Net-(K1B-S)") (class "Default")
      (node (ref "JP3") (pin "1") (pinfunction "1_1") (pintype "passive"))
      (node (ref "K1") (pin "N.O") (pinfunction "S_N.O") (pintype "passive"))
    )
    (net (code "24") (name "Net-(L2-P$1)") (class "Default")
      (node (ref "D4") (pin "C") (pinfunction "C_C") (pintype "passive"))
      (node (ref "D5") (pin "C") (pinfunction "C_C") (pintype "passive"))
      (node (ref "D6") (pin "C") (pinfunction "C_C") (pintype "passive"))
      (node (ref "L2") (pin "1") (pinfunction "P$1_1") (pintype "bidirectional"))
    )
    (net (code "25") (name "Net-(L4-P$1)") (class "Default")
      (node (ref "C1") (pin "1") (pinfunction "1_1") (pintype "passive"))
      (node (ref "L4") (pin "1") (pinfunction "P$1_1") (pintype "bidirectional"))
      (node (ref "U12") (pin "17") (pinfunction "AVDD_17") (pintype "bidirectional"))
    )
    (net (code "26") (name "Net-(L6-P$2)") (class "Default")
      (node (ref "D5") (pin "A") (pinfunction "A_A") (pintype "passive"))
      (node (ref "D6") (pin "A") (pinfunction "A_A") (pintype "passive"))
      (node (ref "JP4") (pin "2") (pinfunction "2_2") (pintype "passive"))
      (node (ref "L6") (pin "2") (pinfunction "P$2_2") (pintype "bidirectional"))
    )
    (net (code "27") (name "Net-(LED1-PadA)") (class "Default")
      (node (ref "LED1") (pin "A") (pinfunction "A_A") (pintype "passive"))
      (node (ref "R24") (pin "1") (pinfunction "1_1") (pintype "passive"))
    )
    (net (code "28") (name "Net-(LED2-PadA)") (class "Default")
      (node (ref "LED2") (pin "A") (pinfunction "A_A") (pintype "passive"))
      (node (ref "R38") (pin "1") (pinfunction "1_1") (pintype "passive"))
    )
    (net (code "29") (name "Net-(LED3-PadA)") (class "Default")
      (node (ref "LED3") (pin "A") (pinfunction "A_A") (pintype "passive"))
      (node (ref "R17") (pin "1") (pinfunction "1_1") (pintype "passive"))
    )
    (net (code "30") (name "Net-(LED4-PadA)") (class "Default")
      (node (ref "LED4") (pin "A") (pinfunction "A_A") (pintype "passive"))
      (node (ref "R6") (pin "2") (pinfunction "2_2") (pintype "passive"))
    )
    (net (code "31") (name "Net-(LED5-PadA)") (class "Default")
      (node (ref "LED5") (pin "A") (pinfunction "A_A") (pintype "passive"))
      (node (ref "R12") (pin "1") (pinfunction "1_1") (pintype "passive"))
    )
    (net (code "32") (name "Net-(LED7-PadA)") (class "Default")
      (node (ref "LED7") (pin "A") (pinfunction "A_A") (pintype "passive"))
      (node (ref "R39") (pin "1") (pinfunction "1_1") (pintype "passive"))
    )
    (net (code "33") (name "Net-(Q1-G)") (class "Default")
      (node (ref "Q1") (pin "1") (pinfunction "G_1") (pintype "passive"))
      (node (ref "R1") (pin "2") (pinfunction "2_2") (pintype "passive"))
      (node (ref "R4") (pin "1") (pinfunction "1_1") (pintype "passive"))
    )
    (net (code "34") (name "Net-(Q2-G)") (class "Default")
      (node (ref "Q2") (pin "1") (pinfunction "G_1") (pintype "passive"))
      (node (ref "Q3") (pin "3") (pinfunction "S_3") (pintype "passive"))
      (node (ref "U15") (pin "2") (pinfunction "V-_2") (pintype "bidirectional"))
    )
    (net (code "35") (name "Net-(Q2-S)") (class "Default")
      (node (ref "Q2") (pin "3") (pinfunction "S_3") (pintype "passive"))
      (node (ref "U15") (pin "1") (pinfunction "OUT_1") (pintype "bidirectional"))
    )
    (net (code "36") (name "Net-(Q3-G)") (class "Default")
      (node (ref "D2") (pin "A") (pinfunction "A_A") (pintype "passive"))
      (node (ref "Q3") (pin "1") (pinfunction "G_1") (pintype "passive"))
      (node (ref "R23") (pin "2") (pinfunction "2_2") (pintype "passive"))
    )
    (net (code "37") (name "Net-(Q4-G)") (class "Default")
      (node (ref "D3") (pin "A") (pinfunction "A_A") (pintype "passive"))
      (node (ref "Q4") (pin "1") (pinfunction "G_1") (pintype "passive"))
      (node (ref "R26") (pin "2") (pinfunction "2_2") (pintype "passive"))
    )
    (net (code "38") (name "Net-(Q4-S)") (class "Default")
      (node (ref "Q4") (pin "3") (pinfunction "S_3") (pintype "passive"))
      (node (ref "Q5") (pin "1") (pinfunction "G_1") (pintype "passive"))
      (node (ref "U16") (pin "2") (pinfunction "V-_2") (pintype "bidirectional"))
    )
    (net (code "39") (name "Net-(Q5-S)") (class "Default")
      (node (ref "Q5") (pin "3") (pinfunction "S_3") (pintype "passive"))
      (node (ref "U16") (pin "1") (pinfunction "OUT_1") (pintype "bidirectional"))
    )
    (net (code "40") (name "Net-(R7-Pad1)") (class "Default")
      (node (ref "R7") (pin "1") (pinfunction "1_1") (pintype "passive"))
      (node (ref "TX1") (pin "A") (pinfunction "A_A") (pintype "passive"))
    )
    (net (code "41") (name "Net-(R8-Pad1)") (class "Default")
      (node (ref "R8") (pin "1") (pinfunction "1_1") (pintype "passive"))
      (node (ref "RX1") (pin "A") (pinfunction "A_A") (pintype "passive"))
    )
    (net (code "42") (name "Net-(R9-Pad1)") (class "Default")
      (node (ref "R9") (pin "1") (pinfunction "1_1") (pintype "passive"))
      (node (ref "RX2") (pin "A") (pinfunction "A_A") (pintype "passive"))
    )
    (net (code "43") (name "Net-(R10-Pad1)") (class "Default")
      (node (ref "R10") (pin "1") (pinfunction "1_1") (pintype "passive"))
      (node (ref "TX2") (pin "A") (pinfunction "A_A") (pintype "passive"))
    )
    (net (code "44") (name "Net-(R30-Pad1)") (class "Default")
      (node (ref "R30") (pin "1") (pinfunction "1_1") (pintype "passive"))
      (node (ref "RX3") (pin "A") (pinfunction "A_A") (pintype "passive"))
    )
    (net (code "45") (name "Net-(R31-Pad1)") (class "Default")
      (node (ref "R31") (pin "1") (pinfunction "1_1") (pintype "passive"))
      (node (ref "TX3") (pin "A") (pinfunction "A_A") (pintype "passive"))
    )
    (net (code "46") (name "Net-(U3-RXD)") (class "Default")
      (node (ref "U3") (pin "5") (pinfunction "RXD_5") (pintype "input"))
      (node (ref "U4") (pin "3") (pinfunction "2Y_3") (pintype "bidirectional"))
    )
    (net (code "47") (name "Net-(U3-RXLED)") (class "Default")
      (node (ref "RX1") (pin "C") (pinfunction "C_C") (pintype "passive"))
      (node (ref "U3") (pin "22") (pinfunction "RXLED_22") (pintype "bidirectional"))
    )
    (net (code "48") (name "Net-(U3-TXD)") (class "Default")
      (node (ref "U3") (pin "1") (pinfunction "TXD_1") (pintype "output"))
      (node (ref "U4") (pin "2") (pinfunction "1A_2") (pintype "bidirectional"))
    )
    (net (code "49") (name "Net-(U3-TXLED)") (class "Default")
      (node (ref "TX1") (pin "C") (pinfunction "C_C") (pintype "passive"))
      (node (ref "U3") (pin "23") (pinfunction "TXLED_23") (pintype "bidirectional"))
    )
    (net (code "50") (name "Net-(U3-USBDM)") (class "Default")
      (node (ref "CN2") (pin "D-") (pinfunction "D-_D-") (pintype "bidirectional"))
      (node (ref "U3") (pin "16") (pinfunction "USBDM_16") (pintype "bidirectional"))
    )
    (net (code "51") (name "Net-(U3-USBDP)") (class "Default")
      (node (ref "CN2") (pin "D+") (pinfunction "D+_D+") (pintype "bidirectional"))
      (node (ref "U3") (pin "15") (pinfunction "USBDP_15") (pintype "bidirectional"))
    )
    (net (code "52") (name "Net-(U4-2OE)") (class "Default")
      (node (ref "R29") (pin "1") (pinfunction "1_1") (pintype "passive"))
      (node (ref "U4") (pin "7") (pinfunction "2OE_7") (pintype "bidirectional"))
    )
    (net (code "53") (name "Net-(U5-A)") (class "Default")
      (node (ref "J4") (pin "1") (pinfunction "1_1") (pintype "passive"))
      (node (ref "U5") (pin "8") (pinfunction "A_8") (pintype "bidirectional"))
    )
    (net (code "54") (name "Net-(U5-B)") (class "Default")
      (node (ref "J4") (pin "2") (pinfunction "2_2") (pintype "passive"))
      (node (ref "U5") (pin "7") (pinfunction "B_7") (pintype "bidirectional"))
    )
    (net (code "55") (name "Net-(U5-Y)") (class "Default")
      (node (ref "J4") (pin "4") (pinfunction "4_4") (pintype "passive"))
      (node (ref "U5") (pin "5") (pinfunction "Y_5") (pintype "bidirectional"))
    )
    (net (code "56") (name "Net-(U5-Z)") (class "Default")
      (node (ref "J4") (pin "3") (pinfunction "3_3") (pintype "passive"))
      (node (ref "U5") (pin "6") (pinfunction "Z_6") (pintype "bidirectional"))
    )
    (net (code "57") (name "Net-(U9-~{RST})") (class "Default")
      (node (ref "SJ3") (pin "1") (pinfunction "1_1") (pintype "passive"))
      (node (ref "U9") (pin "1") (pinfunction "~{RST}_1") (pintype "bidirectional"))
    )
    (net (code "58") (name "Net-(U11-A)") (class "Default")
      (node (ref "J2") (pin "5") (pinfunction "5_5") (pintype "passive"))
      (node (ref "R32") (pin "1") (pinfunction "1_1") (pintype "passive"))
      (node (ref "U11") (pin "8") (pinfunction "A_8") (pintype "bidirectional"))
    )
    (net (code "59") (name "Net-(U11-B)") (class "Default")
      (node (ref "J2") (pin "6") (pinfunction "6_6") (pintype "passive"))
      (node (ref "R32") (pin "2") (pinfunction "2_2") (pintype "passive"))
      (node (ref "U11") (pin "7") (pinfunction "B_7") (pintype "bidirectional"))
    )
    (net (code "60") (name "Net-(U11-DI)") (class "Default")
      (node (ref "JP1") (pin "3") (pinfunction "3_3") (pintype "passive"))
      (node (ref "TX3") (pin "C") (pinfunction "C_C") (pintype "passive"))
      (node (ref "U11") (pin "3") (pinfunction "DI_3") (pintype "bidirectional"))
      (node (ref "U8") (pin "6") (pinfunction "OUTB_6") (pintype "bidirectional"))
    )
    (net (code "61") (name "Net-(U11-RO)") (class "Default")
      (node (ref "JP1") (pin "2") (pinfunction "2_2") (pintype "passive"))
      (node (ref "RX3") (pin "C") (pinfunction "C_C") (pintype "passive"))
      (node (ref "U11") (pin "2") (pinfunction "RO_2") (pintype "bidirectional"))
      (node (ref "U8") (pin "7") (pinfunction "INA_7") (pintype "bidirectional"))
    )
    (net (code "62") (name "Net-(U11-Y)") (class "Default")
      (node (ref "J2") (pin "4") (pinfunction "4_4") (pintype "passive"))
      (node (ref "R33") (pin "1") (pinfunction "1_1") (pintype "passive"))
      (node (ref "U11") (pin "5") (pinfunction "Y_5") (pintype "bidirectional"))
    )
    (net (code "63") (name "Net-(U11-Z)") (class "Default")
      (node (ref "J2") (pin "3") (pinfunction "3_3") (pintype "passive"))
      (node (ref "R33") (pin "2") (pinfunction "2_2") (pintype "passive"))
      (node (ref "U11") (pin "6") (pinfunction "Z_6") (pintype "bidirectional"))
    )
    (net (code "64") (name "Net-(U12-OSC1{slash}CLKI{slash}CN30{slash}RA2)") (class "Default")
      (node (ref "C3") (pin "1") (pinfunction "1_1") (pintype "passive"))
      (node (ref "U12") (pin "30") (pinfunction "OSC1/CLKI/CN30/RA2_30") (pintype "bidirectional"))
      (node (ref "Y1") (pin "1") (pinfunction "1_1") (pintype "passive"))
    )
    (net (code "65") (name "Net-(U12-OSC2{slash}CLKO{slash}CN29{slash}RA3)") (class "Default")
      (node (ref "C24") (pin "1") (pinfunction "1_1") (pintype "passive"))
      (node (ref "U12") (pin "31") (pinfunction "OSC2/CLKO/CN29/RA3_31") (pintype "bidirectional"))
      (node (ref "Y1") (pin "3") (pinfunction "2_3") (pintype "passive"))
    )
    (net (code "66") (name "Net-(U12-PGEC1{slash}AN3{slash}C2IN+{slash}RP1(1){slash}CN5{slash}RB1)") (class "Default")
      (node (ref "R39") (pin "2") (pinfunction "2_2") (pintype "passive"))
      (node (ref "U12") (pin "22") (pinfunction "PGEC1/AN3/C2IN+/RP1(1)/CN5/RB1_22") (pintype "bidirectional"))
    )
    (net (code "67") (name "Net-(U12-PGEC2{slash}RP11(1){slash}CN15{slash}PMD1{slash}RB11*)") (class "Default")
      (node (ref "JP9") (pin "5") (pinfunction "5_5") (pintype "passive"))
      (node (ref "U12") (pin "9") (pinfunction "PGEC2/RP11(1)/CN15/PMD1/RB11*_9") (pintype "bidirectional"))
    )
    (net (code "68") (name "Net-(U12-PGED2{slash}EMCD2{slash}RP10(1){slash}CN16{slash}PMD2{slash}RB10*)") (class "Default")
      (node (ref "JP9") (pin "4") (pinfunction "4_4") (pintype "passive"))
      (node (ref "U12") (pin "8") (pinfunction "PGED2/EMCD2/RP10(1)/CN16/PMD2/RB10*_8") (pintype "bidirectional"))
    )
    (net (code "69") (name "Net-(U12-~{MCLR}*)") (class "Default")
      (node (ref "R16") (pin "2") (pinfunction "2_2") (pintype "passive"))
      (node (ref "U12") (pin "18") (pinfunction "~{MCLR}*_18") (pintype "bidirectional"))
    )
    (net (code "70") (name "Net-(U15--IN)") (class "Default")
      (node (ref "R28") (pin "1") (pinfunction "1_1") (pintype "passive"))
      (node (ref "U15") (pin "3") (pinfunction "-IN_3") (pintype "bidirectional"))
    )
    (net (code "71") (name "Net-(U15-IN+)") (class "Default")
      (node (ref "D2") (pin "C") (pinfunction "C_C") (pintype "passive"))
      (node (ref "JP10") (pin "1") (pinfunction "1_1") (pintype "passive"))
      (node (ref "JP10") (pin "2") (pinfunction "2_2") (pintype "passive"))
      (node (ref "U15") (pin "4") (pinfunction "IN+_4") (pintype "bidirectional"))
      (node (ref "U15") (pin "5") (pinfunction "V+_5") (pintype "bidirectional"))
    )
    (net (code "72") (name "Net-(U16--IN)") (class "Default")
      (node (ref "R27") (pin "1") (pinfunction "1_1") (pintype "passive"))
      (node (ref "U16") (pin "3") (pinfunction "-IN_3") (pintype "bidirectional"))
    )
    (net (code "73") (name "Net-(U16-IN+)") (class "Default")
      (node (ref "JP11") (pin "1") (pinfunction "1_1") (pintype "passive"))
      (node (ref "JP11") (pin "2") (pinfunction "2_2") (pintype "passive"))
      (node (ref "U16") (pin "4") (pinfunction "IN+_4") (pintype "bidirectional"))
    )
    (net (code "74") (name "Net-(U16-V+)") (class "Default")
      (node (ref "D3") (pin "C") (pinfunction "C_C") (pintype "passive"))
      (node (ref "JP6") (pin "1") (pinfunction "1_1") (pintype "passive"))
      (node (ref "JP6") (pin "2") (pinfunction "2_2") (pintype "passive"))
      (node (ref "R27") (pin "2") (pinfunction "2_2") (pintype "passive"))
      (node (ref "U16") (pin "5") (pinfunction "V+_5") (pintype "bidirectional"))
    )
    (net (code "75") (name "Net-(U17-SCL)") (class "Default")
      (node (ref "R34") (pin "1") (pinfunction "1_1") (pintype "passive"))
      (node (ref "U17") (pin "10") (pinfunction "SCL_10") (pintype "bidirectional"))
      (node (ref "U18") (pin "19") (pinfunction "SCL1_19") (pintype "bidirectional"))
    )
    (net (code "76") (name "Net-(U17-SDA)") (class "Default")
      (node (ref "R42") (pin "1") (pinfunction "1_1") (pintype "passive"))
      (node (ref "U17") (pin "9") (pinfunction "SDA_9") (pintype "bidirectional"))
      (node (ref "U18") (pin "18") (pinfunction "SDA1_18") (pintype "bidirectional"))
    )
    (net (code "77") (name "Net-(U18-VSEL)") (class "Default")
      (node (ref "R44") (pin "1") (pinfunction "1_1") (pintype "passive"))
      (node (ref "R45") (pin "2") (pinfunction "2_2") (pintype "passive"))
      (node (ref "U18") (pin "13") (pinfunction "VSEL_13") (pintype "bidirectional"))
    )
    (net (code "78") (name "RE") (class "Default")
      (node (ref "U12") (pin "43") (pinfunction "*INT0/RP7(1)/CN23/PMD5/RB7_43") (pintype "bidirectional"))
    )
    (net (code "79") (name "RX2") (class "Default")
      (node (ref "RX2") (pin "C") (pinfunction "C_C") (pintype "passive"))
      (node (ref "U12") (pin "4") (pinfunction "RP24(1)/CN20/PMA5/RC8*_4") (pintype "bidirectional"))
      (node (ref "U5") (pin "2") (pinfunction "RO_2") (pintype "bidirectional"))
    )
    (net (code "80") (name "RX3") (class "Default")
      (node (ref "U12") (pin "37") (pinfunction "*RP20(1)/CN25/PMA4/RC4_37") (pintype "bidirectional"))
      (node (ref "U4") (pin "6") (pinfunction "1Y_6") (pintype "bidirectional"))
    )
    (net (code "81") (name "SCL") (class "Default")
      (node (ref "Q11") (pin "3") (pinfunction "D_3") (pintype "passive"))
      (node (ref "R2") (pin "1") (pinfunction "1_1") (pintype "passive"))
      (node (ref "U18") (pin "2") (pinfunction "SCL_2") (pintype "bidirectional"))
    )
    (net (code "82") (name "SDA") (class "Default")
      (node (ref "Q12") (pin "3") (pinfunction "D_3") (pintype "passive"))
      (node (ref "R5") (pin "1") (pinfunction "1_1") (pintype "passive"))
      (node (ref "U18") (pin "3") (pinfunction "SDA_3") (pintype "bidirectional"))
    )
    (net (code "83") (name "TX2") (class "Default")
      (node (ref "TX2") (pin "C") (pinfunction "C_C") (pintype "passive"))
      (node (ref "U12") (pin "5") (pinfunction "RP25(1)/CN19/PMA6/RC9*_5") (pintype "bidirectional"))
      (node (ref "U5") (pin "3") (pinfunction "DI_3") (pintype "bidirectional"))
    )
    (net (code "84") (name "TX3") (class "Default")
      (node (ref "U12") (pin "38") (pinfunction "*RP21(1)/CN26/PMA3/RC5_38") (pintype "bidirectional"))
      (node (ref "U4") (pin "5") (pinfunction "2A_5") (pintype "bidirectional"))
    )
    (net (code "85") (name "V+") (class "Default")
      (node (ref "C25") (pin "1") (pinfunction "1_1") (pintype "passive"))
      (node (ref "C26") (pin "+") (pinfunction "+_+") (pintype "passive"))
      (node (ref "J2") (pin "1") (pinfunction "1_1") (pintype "passive"))
      (node (ref "J2") (pin "2") (pinfunction "2_2") (pintype "passive"))
      (node (ref "R30") (pin "2") (pinfunction "2_2") (pintype "passive"))
      (node (ref "R31") (pin "2") (pinfunction "2_2") (pintype "passive"))
      (node (ref "R6") (pin "1") (pinfunction "1_1") (pintype "passive"))
      (node (ref "U11") (pin "1") (pinfunction "VCC_1") (pintype "bidirectional"))
      (node (ref "U21") (pin "14") (pinfunction "VOUT+_14") (pintype "bidirectional"))
      (node (ref "U8") (pin "8") (pinfunction "VCC2_8") (pintype "bidirectional"))
      (node (ref "V+") (pin "1") (pinfunction "1_1") (pintype "passive"))
    )
    (net (code "86") (name "V-") (class "Default")
      (node (ref "C14") (pin "C") (pinfunction "-_C") (pintype "passive"))
      (node (ref "C17") (pin "2") (pinfunction "2_2") (pintype "passive"))
      (node (ref "C20") (pin "C") (pinfunction "-_C") (pintype "passive"))
      (node (ref "C27") (pin "2") (pinfunction "2_2") (pintype "passive"))
      (node (ref "JP2") (pin "1") (pinfunction "1_1") (pintype "passive"))
      (node (ref "JP2") (pin "2") (pinfunction "2_2") (pintype "passive"))
      (node (ref "Q3") (pin "2") (pinfunction "D_2") (pintype "passive"))
      (node (ref "Q4") (pin "2") (pinfunction "D_2") (pintype "passive"))
      (node (ref "R21") (pin "1") (pinfunction "1_1") (pintype "passive"))
      (node (ref "R23") (pin "1") (pinfunction "1_1") (pintype "passive"))
      (node (ref "R25") (pin "1") (pinfunction "1_1") (pintype "passive"))
      (node (ref "R26") (pin "1") (pinfunction "1_1") (pintype "passive"))
      (node (ref "R45") (pin "1") (pinfunction "1_1") (pintype "passive"))
      (node (ref "U17") (pin "1") (pinfunction "ADDR_1") (pintype "bidirectional"))
      (node (ref "U17") (pin "3") (pinfunction "GND_3") (pintype "bidirectional"))
      (node (ref "U18") (pin "11") (pinfunction "GNDISO_11") (pintype "bidirectional"))
      (node (ref "U18") (pin "14") (pinfunction "GNDISO_14") (pintype "bidirectional"))
      (node (ref "U18") (pin "16") (pinfunction "GNDISO_16") (pintype "bidirectional"))
      (node (ref "U18") (pin "20") (pinfunction "GNDISO_20") (pintype "bidirectional"))
    )
    (net (code "87") (name "WDI") (class "Default")
      (node (ref "U12") (pin "10") (pinfunction "AN12/DAC1RP/RP12(1)/CN14/PMD0/RB12_10") (pintype "bidirectional"))
      (node (ref "U9") (pin "4") (pinfunction "WDI_4") (pintype "bidirectional"))
    )
    (net (code "88") (name "unconnected-(CN2-PadID)") (class "Default")
      (node (ref "CN2") (pin "ID") (pinfunction "ID_ID") (pintype "bidirectional"))
    )
    (net (code "89") (name "unconnected-(U3-CTS-Pad11)") (class "Default")
      (node (ref "U3") (pin "11") (pinfunction "CTS_11") (pintype "bidirectional"))
    )
    (net (code "90") (name "unconnected-(U3-DTR-Pad2)") (class "Default")
      (node (ref "U3") (pin "2") (pinfunction "DTR_2") (pintype "bidirectional"))
    )
    (net (code "91") (name "unconnected-(U3-RTS-Pad3)") (class "Default")
      (node (ref "U3") (pin "3") (pinfunction "RTS_3") (pintype "bidirectional"))
    )
    (net (code "92") (name "unconnected-(U9-~{MR}-Pad3)") (class "Default")
      (node (ref "U9") (pin "3") (pinfunction "~{MR}_3") (pintype "bidirectional"))
    )
    (net (code "93") (name "unconnected-(U12-*PGEC3{slash}ASCL1{slash}RP6(1){slash}CN24{slash}PMD6{slash}RB6-Pad42)") (class "Default")
      (node (ref "U12") (pin "42") (pinfunction "*PGEC3/ASCL1/RP6(1)/CN24/PMD6/RB6_42") (pintype "bidirectional"))
    )
    (net (code "94") (name "unconnected-(U12-*PGED3{slash}ASDA1{slash}RP5(1){slash}CN27{slash}PMD7{slash}RB5-Pad41)") (class "Default")
      (node (ref "U12") (pin "41") (pinfunction "*PGED3/ASDA1/RP5(1)/CN27/PMD7/RB5_41") (pintype "bidirectional"))
    )
    (net (code "95") (name "unconnected-(U12-*RP19(1){slash}CN28{slash}PMBE{slash}RC3-Pad36)") (class "Default")
      (node (ref "U12") (pin "36") (pinfunction "*RP19(1)/CN28/PMBE/RC3_36") (pintype "bidirectional"))
    )
    (net (code "96") (name "unconnected-(U12-*TDI{slash}PMA9{slash}RA9-Pad35)") (class "Default")
      (node (ref "U12") (pin "35") (pinfunction "*TDI/PMA9/RA9_35") (pintype "bidirectional"))
    )
    (net (code "97") (name "unconnected-(U12-*TDO{slash}PMA8{slash}RA8-Pad32)") (class "Default")
      (node (ref "U12") (pin "32") (pinfunction "*TDO/PMA8/RA8_32") (pintype "bidirectional"))
    )
    (net (code "98") (name "unconnected-(U12-AN0{slash}VREF+{slash}CN2{slash}RA0-Pad19)") (class "Default")
      (node (ref "U12") (pin "19") (pinfunction "AN0/VREF+/CN2/RA0_19") (pintype "bidirectional"))
    )
    (net (code "99") (name "unconnected-(U12-AN1{slash}VREF-{slash}CN3{slash}RA1-Pad20)") (class "Default")
      (node (ref "U12") (pin "20") (pinfunction "AN1/VREF-/CN3/RA1_20") (pintype "bidirectional"))
    )
    (net (code "100") (name "unconnected-(U12-AN4{slash}C1IN-{slash}RP2(1){slash}CN6{slash}RB2-Pad23)") (class "Default")
      (node (ref "U12") (pin "23") (pinfunction "AN4/C1IN-/RP2(1)/CN6/RB2_23") (pintype "bidirectional"))
    )
    (net (code "101") (name "unconnected-(U12-AN5{slash}C1IN+{slash}RP3(1){slash}CN7{slash}RB3-Pad24)") (class "Default")
      (node (ref "U12") (pin "24") (pinfunction "AN5/C1IN+/RP3(1)/CN7/RB3_24") (pintype "bidirectional"))
    )
    (net (code "102") (name "unconnected-(U12-AN6{slash}DAC1RM{slash}RP16(1){slash}CN8{slash}RC0-Pad25)") (class "Default")
      (node (ref "U12") (pin "25") (pinfunction "AN6/DAC1RM/RP16(1)/CN8/RC0_25") (pintype "bidirectional"))
    )
    (net (code "103") (name "unconnected-(U12-AN7{slash}DAC1LM{slash}RP17{slash}(1){slash}CN9{slash}RC1-Pad26)") (class "Default")
      (node (ref "U12") (pin "26") (pinfunction "AN7/DAC1LM/RP17/(1)/CN9/RC1_26") (pintype "bidirectional"))
    )
    (net (code "104") (name "unconnected-(U12-AN8{slash}CVREF{slash}RP18(1){slash}PMA2{slash}CN10{slash}RC2-Pad27)") (class "Default")
      (node (ref "U12") (pin "27") (pinfunction "AN8/CVREF/RP18(1)/PMA2/CN10/RC2_27") (pintype "bidirectional"))
    )
    (net (code "105") (name "unconnected-(U12-AN9{slash}DAC1LN{slash}RP15(1){slash}CN11{slash}PMCS1{slash}RB15*-Pad15)") (class "Default")
      (node (ref "U12") (pin "15") (pinfunction "AN9/DAC1LN/RP15(1)/CN11/PMCS1/RB15*_15") (pintype "bidirectional"))
    )
    (net (code "106") (name "unconnected-(U12-AN10{slash}DAC1LP{slash}RTCC{slash}RP14*-Pad14)") (class "Default")
      (node (ref "U12") (pin "14") (pinfunction "AN10/DAC1LP/RTCC/RP14*_14") (pintype "bidirectional"))
    )
    (net (code "107") (name "unconnected-(U12-AN11{slash}DAC1RN{slash}RP13(1){slash}CN13{slash}PMRD{slash}RB13-Pad11)") (class "Default")
      (node (ref "U12") (pin "11") (pinfunction "AN11/DAC1RN/RP13(1)/CN13/PMRD/RB13_11") (pintype "bidirectional"))
    )
    (net (code "108") (name "unconnected-(U12-PGED1{slash}AN2{slash}C2IN-{slash}RP0(1){slash}CN4{slash}RB0-Pad21)") (class "Default")
      (node (ref "U12") (pin "21") (pinfunction "PGED1/AN2/C2IN-/RP0(1)/CN4/RB0_21") (pintype "bidirectional"))
    )
    (net (code "109") (name "unconnected-(U12-SOSCI{slash}RP4(1){slash}CN1{slash}RB4-Pad33)") (class "Default")
      (node (ref "U12") (pin "33") (pinfunction "SOSCI/RP4(1)/CN1/RB4_33") (pintype "bidirectional"))
    )
    (net (code "110") (name "unconnected-(U12-SOSCO{slash}T1CK{slash}CN0{slash}RA4-Pad34)") (class "Default")
      (node (ref "U12") (pin "34") (pinfunction "SOSCO/T1CK/CN0/RA4_34") (pintype "bidirectional"))
    )
    (net (code "111") (name "unconnected-(U12-TCK{slash}PMA7{slash}RA7*-Pad13)") (class "Default")
      (node (ref "U12") (pin "13") (pinfunction "TCK/PMA7/RA7*_13") (pintype "bidirectional"))
    )
    (net (code "112") (name "unconnected-(U12-TMS{slash}PMA10{slash}RA10*-Pad12)") (class "Default")
      (node (ref "U12") (pin "12") (pinfunction "TMS/PMA10/RA10*_12") (pintype "bidirectional"))
    )
    (net (code "113") (name "unconnected-(U17-AIN2-Pad6)") (class "Default")
      (node (ref "U17") (pin "6") (pinfunction "AIN2_6") (pintype "bidirectional"))
    )
    (net (code "114") (name "unconnected-(U17-AIN3-Pad7)") (class "Default")
      (node (ref "U17") (pin "7") (pinfunction "AIN3_7") (pintype "bidirectional"))
    )
    (net (code "115") (name "unconnected-(U17-ALERT{slash}RDY-Pad2)") (class "Default")
      (node (ref "U17") (pin "2") (pinfunction "ALERT/RDY_2") (pintype "bidirectional"))
    )
    (net (code "116") (name "unconnected-(U18-PDIS-Pad8)") (class "Default")
      (node (ref "U18") (pin "8") (pinfunction "PDIS_8") (pintype "bidirectional"))
    )
    (net (code "117") (name "unconnected-(U21-~{CTL}-Pad1)") (class "Default")
      (node (ref "U21") (pin "1") (pinfunction "~{CTL}_1") (pintype "bidirectional"))
    )
  )
)
